# Fluid_Valve_CTRL.net
KiCad netlist of a schematic drawn in Altium Designer
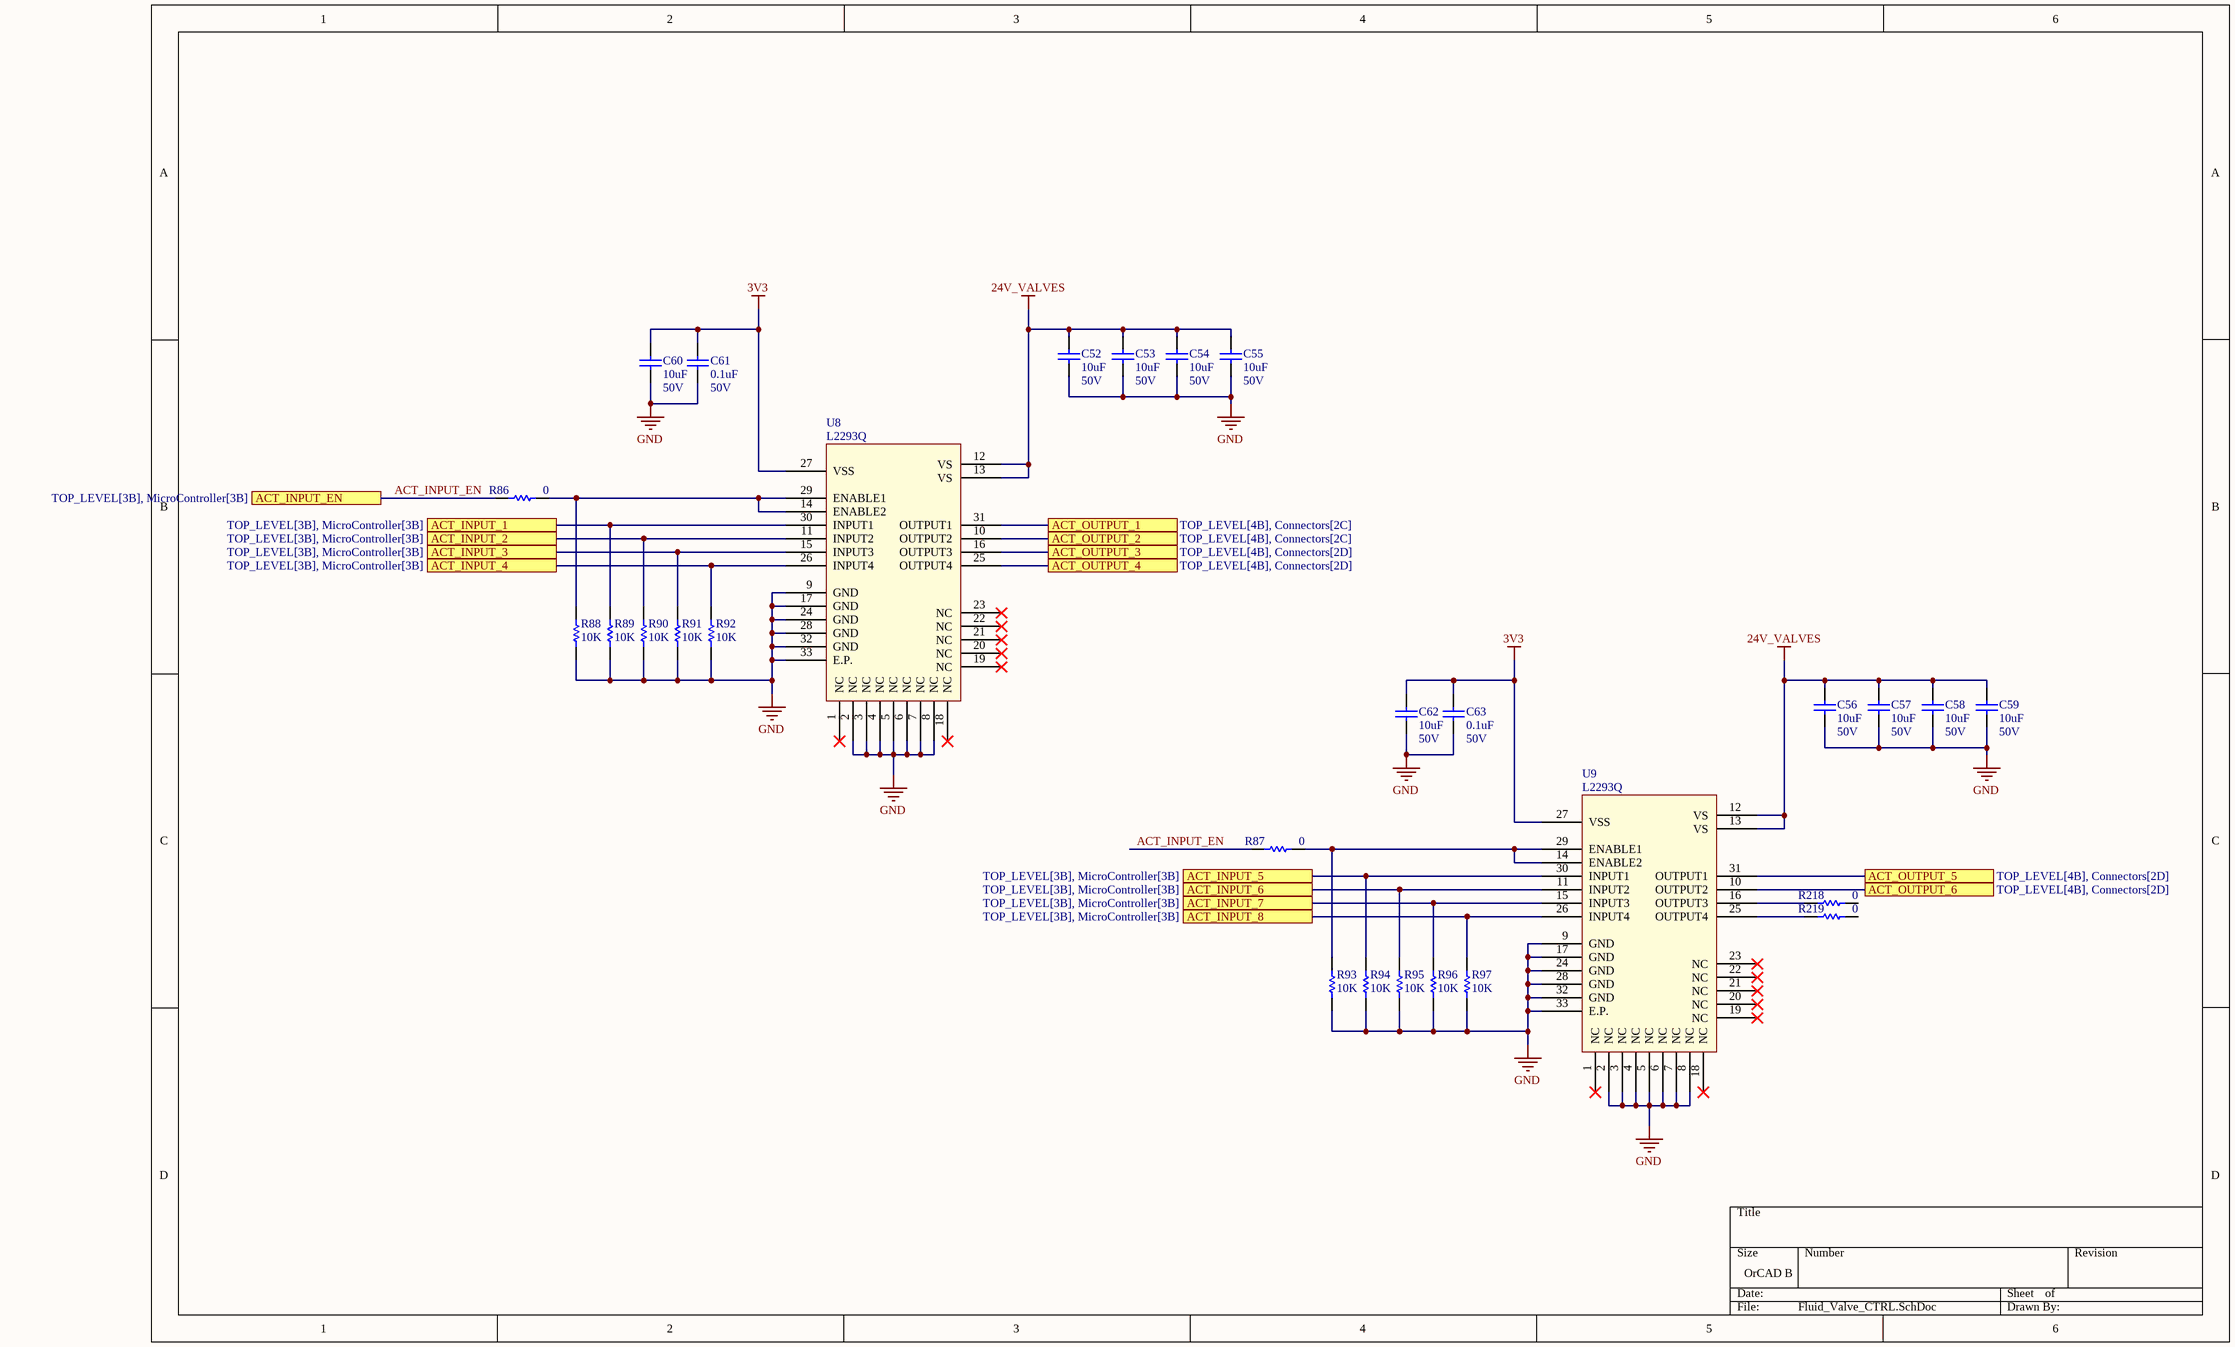
[diagram p0: Fluid_Valve_CTRL.SchDoc]

(export (version "E")
  (design (tool "Eeschema 10.0.6"))
  (components
    (comp (ref "C52")
      (value "10uF")
      (footprint "DEFAULT_CAPACITOR_0805")
      (description "CAP CER 10UF 50V X5R 0805")
      (fields (field (name "RATING") "50V") (field (name "Comment") "GRM21BR61H106KE43L"))
      (libsource (lib "Avery Altium Llibrary") (part "GRM21BR61H106KE43L"))
    )
    (comp (ref "C53")
      (value "10uF")
      (footprint "DEFAULT_CAPACITOR_0805")
      (description "CAP CER 10UF 50V X5R 0805")
      (fields (field (name "RATING") "50V") (field (name "Comment") "GRM21BR61H106KE43L"))
      (libsource (lib "Avery Altium Llibrary") (part "GRM21BR61H106KE43L"))
    )
    (comp (ref "C54")
      (value "10uF")
      (footprint "DEFAULT_CAPACITOR_0805")
      (description "CAP CER 10UF 50V X5R 0805")
      (fields (field (name "RATING") "50V") (field (name "Comment") "GRM21BR61H106KE43L"))
      (libsource (lib "Avery Altium Llibrary") (part "GRM21BR61H106KE43L"))
    )
    (comp (ref "C55")
      (value "10uF")
      (footprint "DEFAULT_CAPACITOR_0805")
      (description "CAP CER 10UF 50V X5R 0805")
      (fields (field (name "RATING") "50V") (field (name "Comment") "GRM21BR61H106KE43L"))
      (libsource (lib "Avery Altium Llibrary") (part "GRM21BR61H106KE43L"))
    )
    (comp (ref "C56")
      (value "10uF")
      (footprint "DEFAULT_CAPACITOR_0805")
      (description "CAP CER 10UF 50V X5R 0805")
      (fields (field (name "RATING") "50V") (field (name "Comment") "GRM21BR61H106KE43L"))
      (libsource (lib "Avery Altium Llibrary") (part "GRM21BR61H106KE43L"))
    )
    (comp (ref "C57")
      (value "10uF")
      (footprint "DEFAULT_CAPACITOR_0805")
      (description "CAP CER 10UF 50V X5R 0805")
      (fields (field (name "RATING") "50V") (field (name "Comment") "GRM21BR61H106KE43L"))
      (libsource (lib "Avery Altium Llibrary") (part "GRM21BR61H106KE43L"))
    )
    (comp (ref "C58")
      (value "10uF")
      (footprint "DEFAULT_CAPACITOR_0805")
      (description "CAP CER 10UF 50V X5R 0805")
      (fields (field (name "RATING") "50V") (field (name "Comment") "GRM21BR61H106KE43L"))
      (libsource (lib "Avery Altium Llibrary") (part "GRM21BR61H106KE43L"))
    )
    (comp (ref "C59")
      (value "10uF")
      (footprint "DEFAULT_CAPACITOR_0805")
      (description "CAP CER 10UF 50V X5R 0805")
      (fields (field (name "RATING") "50V") (field (name "Comment") "GRM21BR61H106KE43L"))
      (libsource (lib "Avery Altium Llibrary") (part "GRM21BR61H106KE43L"))
    )
    (comp (ref "C60")
      (value "10uF")
      (footprint "DEFAULT_CAPACITOR_0805")
      (description "CAP CER 10UF 50V X5R 0805")
      (fields (field (name "RATING") "50V") (field (name "Comment") "GRM21BR61H106KE43L"))
      (libsource (lib "Avery Altium Llibrary") (part "GRM21BR61H106KE43L"))
    )
    (comp (ref "C61")
      (value "0.1uF")
      (footprint "DEFAULT_CAPACITOR_0805")
      (description "CAP CER 0.1UF 50V X7R 0805")
      (fields
        (field (name "MANUFACTURER") "Cal-Chip Electronics, Inc.")
        (field (name "RATING") "50V")
        (field (name "Comment") "KGM21NR71H104KT")
      )
      (libsource (lib "Avery Altium Llibrary") (part "KGM21NR71H104KT"))
    )
    (comp (ref "C62")
      (value "10uF")
      (footprint "DEFAULT_CAPACITOR_0805")
      (description "CAP CER 10UF 50V X5R 0805")
      (fields (field (name "RATING") "50V") (field (name "Comment") "GRM21BR61H106KE43L"))
      (libsource (lib "Avery Altium Llibrary") (part "GRM21BR61H106KE43L"))
    )
    (comp (ref "C63")
      (value "0.1uF")
      (footprint "DEFAULT_CAPACITOR_0805")
      (description "CAP CER 0.1UF 50V X7R 0805")
      (fields
        (field (name "MANUFACTURER") "Cal-Chip Electronics, Inc.")
        (field (name "RATING") "50V")
        (field (name "Comment") "KGM21NR71H104KT")
      )
      (libsource (lib "Avery Altium Llibrary") (part "KGM21NR71H104KT"))
    )
    (comp (ref "R86")
      (value "0")
      (footprint "DEFAULT_RESISTOR_0805")
      (description "RES 0 OHM JUMPER 1/8W 0805")
      (fields (field (name "POWER") "1/8W") (field (name "Comment") "RC0805JR-070RL"))
      (libsource (lib "Avery Altium Llibrary") (part "RC0805JR-070RL"))
    )
    (comp (ref "R87")
      (value "0")
      (footprint "DEFAULT_RESISTOR_0805")
      (description "RES 0 OHM JUMPER 1/8W 0805")
      (fields (field (name "POWER") "1/8W") (field (name "Comment") "RC0805JR-070RL"))
      (libsource (lib "Avery Altium Llibrary") (part "RC0805JR-070RL"))
    )
    (comp (ref "R88")
      (value "10K")
      (footprint "DEFAULT_RESISTOR_0805")
      (description "RES SMD 10K OHM 1% 1/4W 0805")
      (fields (field (name "POWER") "1/4W") (field (name "TOLERANCE") "1%"))
      (libsource (lib "Avery Altium Llibrary") (part "CRCW080510K0FKEA"))
    )
    (comp (ref "R89")
      (value "10K")
      (footprint "DEFAULT_RESISTOR_0805")
      (description "RES SMD 10K OHM 1% 1/4W 0805")
      (fields (field (name "POWER") "1/4W") (field (name "TOLERANCE") "1%"))
      (libsource (lib "Avery Altium Llibrary") (part "CRCW080510K0FKEA"))
    )
    (comp (ref "R90")
      (value "10K")
      (footprint "DEFAULT_RESISTOR_0805")
      (description "RES SMD 10K OHM 1% 1/4W 0805")
      (fields (field (name "POWER") "1/4W") (field (name "TOLERANCE") "1%"))
      (libsource (lib "Avery Altium Llibrary") (part "CRCW080510K0FKEA"))
    )
    (comp (ref "R91")
      (value "10K")
      (footprint "DEFAULT_RESISTOR_0805")
      (description "RES SMD 10K OHM 1% 1/4W 0805")
      (fields (field (name "POWER") "1/4W") (field (name "TOLERANCE") "1%"))
      (libsource (lib "Avery Altium Llibrary") (part "CRCW080510K0FKEA"))
    )
    (comp (ref "R92")
      (value "10K")
      (footprint "DEFAULT_RESISTOR_0805")
      (description "RES SMD 10K OHM 1% 1/4W 0805")
      (fields (field (name "POWER") "1/4W") (field (name "TOLERANCE") "1%"))
      (libsource (lib "Avery Altium Llibrary") (part "CRCW080510K0FKEA"))
    )
    (comp (ref "R93")
      (value "10K")
      (footprint "DEFAULT_RESISTOR_0805")
      (description "RES SMD 10K OHM 1% 1/4W 0805")
      (fields (field (name "POWER") "1/4W") (field (name "TOLERANCE") "1%"))
      (libsource (lib "Avery Altium Llibrary") (part "CRCW080510K0FKEA"))
    )
    (comp (ref "R94")
      (value "10K")
      (footprint "DEFAULT_RESISTOR_0805")
      (description "RES SMD 10K OHM 1% 1/4W 0805")
      (fields (field (name "POWER") "1/4W") (field (name "TOLERANCE") "1%"))
      (libsource (lib "Avery Altium Llibrary") (part "CRCW080510K0FKEA"))
    )
    (comp (ref "R95")
      (value "10K")
      (footprint "DEFAULT_RESISTOR_0805")
      (description "RES SMD 10K OHM 1% 1/4W 0805")
      (fields (field (name "POWER") "1/4W") (field (name "TOLERANCE") "1%"))
      (libsource (lib "Avery Altium Llibrary") (part "CRCW080510K0FKEA"))
    )
    (comp (ref "R96")
      (value "10K")
      (footprint "DEFAULT_RESISTOR_0805")
      (description "RES SMD 10K OHM 1% 1/4W 0805")
      (fields (field (name "POWER") "1/4W") (field (name "TOLERANCE") "1%"))
      (libsource (lib "Avery Altium Llibrary") (part "CRCW080510K0FKEA"))
    )
    (comp (ref "R97")
      (value "10K")
      (footprint "DEFAULT_RESISTOR_0805")
      (description "RES SMD 10K OHM 1% 1/4W 0805")
      (fields (field (name "POWER") "1/4W") (field (name "TOLERANCE") "1%"))
      (libsource (lib "Avery Altium Llibrary") (part "CRCW080510K0FKEA"))
    )
    (comp (ref "R218")
      (value "0")
      (footprint "DEFAULT_RESISTOR_0805")
      (description "RES 0 OHM JUMPER 1/8W 0805")
      (fields (field (name "POWER") "1/8W") (field (name "Comment") "RC0805JR-070RL"))
      (libsource (lib "Avery Altium Llibrary") (part "RC0805JR-070RL"))
    )
    (comp (ref "R219")
      (value "0")
      (footprint "DEFAULT_RESISTOR_0805")
      (description "RES 0 OHM JUMPER 1/8W 0805")
      (fields (field (name "POWER") "1/8W") (field (name "Comment") "RC0805JR-070RL"))
      (libsource (lib "Avery Altium Llibrary") (part "RC0805JR-070RL"))
    )
    (comp (ref "U8")
      (value "L2293Q")
      (footprint "L2293Q")
      (description "IC HALF BRIDG DRV 600MA 32VFQFPN")
      (fields (field (name "MANUFACTURER") "STMicroelectronics") (field (name "MANUFACTURER P/N") "L2293Q"))
      (libsource (lib "Avery Altium Llibrary") (part "L2293Q"))
    )
    (comp (ref "U9")
      (value "L2293Q")
      (footprint "L2293Q")
      (description "IC HALF BRIDG DRV 600MA 32VFQFPN")
      (fields (field (name "MANUFACTURER") "STMicroelectronics") (field (name "MANUFACTURER P/N") "L2293Q"))
      (libsource (lib "Avery Altium Llibrary") (part "L2293Q"))
    )
  )
  (nets
    (net (code "1") (name "/ACT_INPUT_1") (class "Default")
      (node (ref "R89") (pin "1") (pinfunction "1_1") (pintype "passive"))
      (node (ref "U8") (pin "30") (pinfunction "INPUT1_30") (pintype "passive"))
    )
    (net (code "2") (name "/ACT_INPUT_2") (class "Default")
      (node (ref "R90") (pin "1") (pinfunction "1_1") (pintype "passive"))
      (node (ref "U8") (pin "11") (pinfunction "INPUT2_11") (pintype "passive"))
    )
    (net (code "3") (name "/ACT_INPUT_3") (class "Default")
      (node (ref "R91") (pin "1") (pinfunction "1_1") (pintype "passive"))
      (node (ref "U8") (pin "15") (pinfunction "INPUT3_15") (pintype "passive"))
    )
    (net (code "4") (name "/ACT_INPUT_4") (class "Default")
      (node (ref "R92") (pin "1") (pinfunction "1_1") (pintype "passive"))
      (node (ref "U8") (pin "26") (pinfunction "INPUT4_26") (pintype "passive"))
    )
    (net (code "5") (name "/ACT_INPUT_5") (class "Default")
      (node (ref "R94") (pin "1") (pinfunction "1_1") (pintype "passive"))
      (node (ref "U9") (pin "30") (pinfunction "INPUT1_30") (pintype "passive"))
    )
    (net (code "6") (name "/ACT_INPUT_6") (class "Default")
      (node (ref "R95") (pin "1") (pinfunction "1_1") (pintype "passive"))
      (node (ref "U9") (pin "11") (pinfunction "INPUT2_11") (pintype "passive"))
    )
    (net (code "7") (name "/ACT_INPUT_7") (class "Default")
      (node (ref "R96") (pin "1") (pinfunction "1_1") (pintype "passive"))
      (node (ref "U9") (pin "15") (pinfunction "INPUT3_15") (pintype "passive"))
    )
    (net (code "8") (name "/ACT_INPUT_8") (class "Default")
      (node (ref "R97") (pin "1") (pinfunction "1_1") (pintype "passive"))
      (node (ref "U9") (pin "26") (pinfunction "INPUT4_26") (pintype "passive"))
    )
    (net (code "9") (name "/ACT_INPUT_EN") (class "Default")
      (node (ref "R86") (pin "2") (pinfunction "2_2") (pintype "passive"))
      (node (ref "R87") (pin "2") (pinfunction "2_2") (pintype "passive"))
    )
    (net (code "10") (name "/ACT_OUTPUT_1") (class "Default")
      (node (ref "U8") (pin "31") (pinfunction "OUTPUT1_31") (pintype "passive"))
    )
    (net (code "11") (name "/ACT_OUTPUT_2") (class "Default")
      (node (ref "U8") (pin "10") (pinfunction "OUTPUT2_10") (pintype "passive"))
    )
    (net (code "12") (name "/ACT_OUTPUT_3") (class "Default")
      (node (ref "U8") (pin "16") (pinfunction "OUTPUT3_16") (pintype "passive"))
    )
    (net (code "13") (name "/ACT_OUTPUT_4") (class "Default")
      (node (ref "U8") (pin "25") (pinfunction "OUTPUT4_25") (pintype "passive"))
    )
    (net (code "14") (name "/ACT_OUTPUT_5") (class "Default")
      (node (ref "U9") (pin "31") (pinfunction "OUTPUT1_31") (pintype "passive"))
    )
    (net (code "15") (name "/ACT_OUTPUT_6") (class "Default")
      (node (ref "U9") (pin "10") (pinfunction "OUTPUT2_10") (pintype "passive"))
    )
    (net (code "16") (name "3V3") (class "Default")
      (node (ref "C60") (pin "2") (pinfunction "2_2") (pintype "passive"))
      (node (ref "C61") (pin "2") (pinfunction "2_2") (pintype "passive"))
      (node (ref "C62") (pin "2") (pinfunction "2_2") (pintype "passive"))
      (node (ref "C63") (pin "2") (pinfunction "2_2") (pintype "passive"))
      (node (ref "U8") (pin "27") (pinfunction "VSS_27") (pintype "passive"))
      (node (ref "U9") (pin "27") (pinfunction "VSS_27") (pintype "passive"))
    )
    (net (code "17") (name "24V_VALVES") (class "Default")
      (node (ref "C52") (pin "2") (pinfunction "2_2") (pintype "passive"))
      (node (ref "C53") (pin "2") (pinfunction "2_2") (pintype "passive"))
      (node (ref "C54") (pin "2") (pinfunction "2_2") (pintype "passive"))
      (node (ref "C55") (pin "2") (pinfunction "2_2") (pintype "passive"))
      (node (ref "C56") (pin "2") (pinfunction "2_2") (pintype "passive"))
      (node (ref "C57") (pin "2") (pinfunction "2_2") (pintype "passive"))
      (node (ref "C58") (pin "2") (pinfunction "2_2") (pintype "passive"))
      (node (ref "C59") (pin "2") (pinfunction "2_2") (pintype "passive"))
      (node (ref "U8") (pin "12") (pinfunction "VS_12") (pintype "passive"))
      (node (ref "U8") (pin "13") (pinfunction "VS_13") (pintype "passive"))
      (node (ref "U9") (pin "12") (pinfunction "VS_12") (pintype "passive"))
      (node (ref "U9") (pin "13") (pinfunction "VS_13") (pintype "passive"))
    )
    (net (code "18") (name "GND") (class "Default")
      (node (ref "C52") (pin "1") (pinfunction "1_1") (pintype "passive"))
      (node (ref "C53") (pin "1") (pinfunction "1_1") (pintype "passive"))
      (node (ref "C54") (pin "1") (pinfunction "1_1") (pintype "passive"))
      (node (ref "C55") (pin "1") (pinfunction "1_1") (pintype "passive"))
      (node (ref "C56") (pin "1") (pinfunction "1_1") (pintype "passive"))
      (node (ref "C57") (pin "1") (pinfunction "1_1") (pintype "passive"))
      (node (ref "C58") (pin "1") (pinfunction "1_1") (pintype "passive"))
      (node (ref "C59") (pin "1") (pinfunction "1_1") (pintype "passive"))
      (node (ref "C60") (pin "1") (pinfunction "1_1") (pintype "passive"))
      (node (ref "C61") (pin "1") (pinfunction "1_1") (pintype "passive"))
      (node (ref "C62") (pin "1") (pinfunction "1_1") (pintype "passive"))
      (node (ref "C63") (pin "1") (pinfunction "1_1") (pintype "passive"))
      (node (ref "R88") (pin "2") (pinfunction "2_2") (pintype "passive"))
      (node (ref "R89") (pin "2") (pinfunction "2_2") (pintype "passive"))
      (node (ref "R90") (pin "2") (pinfunction "2_2") (pintype "passive"))
      (node (ref "R91") (pin "2") (pinfunction "2_2") (pintype "passive"))
      (node (ref "R92") (pin "2") (pinfunction "2_2") (pintype "passive"))
      (node (ref "R93") (pin "2") (pinfunction "2_2") (pintype "passive"))
      (node (ref "R94") (pin "2") (pinfunction "2_2") (pintype "passive"))
      (node (ref "R95") (pin "2") (pinfunction "2_2") (pintype "passive"))
      (node (ref "R96") (pin "2") (pinfunction "2_2") (pintype "passive"))
      (node (ref "R97") (pin "2") (pinfunction "2_2") (pintype "passive"))
      (node (ref "U8") (pin "17") (pinfunction "GND_17") (pintype "passive"))
      (node (ref "U8") (pin "2") (pinfunction "NC_2") (pintype "passive"))
      (node (ref "U8") (pin "24") (pinfunction "GND_24") (pintype "passive"))
      (node (ref "U8") (pin "28") (pinfunction "GND_28") (pintype "passive"))
      (node (ref "U8") (pin "3") (pinfunction "NC_3") (pintype "passive"))
      (node (ref "U8") (pin "32") (pinfunction "GND_32") (pintype "passive"))
      (node (ref "U8") (pin "33") (pinfunction "E.P._33") (pintype "passive"))
      (node (ref "U8") (pin "4") (pinfunction "NC_4") (pintype "passive"))
      (node (ref "U8") (pin "5") (pinfunction "NC_5") (pintype "passive"))
      (node (ref "U8") (pin "6") (pinfunction "NC_6") (pintype "passive"))
      (node (ref "U8") (pin "7") (pinfunction "NC_7") (pintype "passive"))
      (node (ref "U8") (pin "8") (pinfunction "NC_8") (pintype "passive"))
      (node (ref "U8") (pin "9") (pinfunction "GND_9") (pintype "passive"))
      (node (ref "U9") (pin "17") (pinfunction "GND_17") (pintype "passive"))
      (node (ref "U9") (pin "2") (pinfunction "NC_2") (pintype "passive"))
      (node (ref "U9") (pin "24") (pinfunction "GND_24") (pintype "passive"))
      (node (ref "U9") (pin "28") (pinfunction "GND_28") (pintype "passive"))
      (node (ref "U9") (pin "3") (pinfunction "NC_3") (pintype "passive"))
      (node (ref "U9") (pin "32") (pinfunction "GND_32") (pintype "passive"))
      (node (ref "U9") (pin "33") (pinfunction "E.P._33") (pintype "passive"))
      (node (ref "U9") (pin "4") (pinfunction "NC_4") (pintype "passive"))
      (node (ref "U9") (pin "5") (pinfunction "NC_5") (pintype "passive"))
      (node (ref "U9") (pin "6") (pinfunction "NC_6") (pintype "passive"))
      (node (ref "U9") (pin "7") (pinfunction "NC_7") (pintype "passive"))
      (node (ref "U9") (pin "8") (pinfunction "NC_8") (pintype "passive"))
      (node (ref "U9") (pin "9") (pinfunction "GND_9") (pintype "passive"))
    )
    (net (code "19") (name "Net-(U8-ENABLE1)") (class "Default")
      (node (ref "R86") (pin "1") (pinfunction "1_1") (pintype "passive"))
      (node (ref "R88") (pin "1") (pinfunction "1_1") (pintype "passive"))
      (node (ref "U8") (pin "14") (pinfunction "ENABLE2_14") (pintype "passive"))
      (node (ref "U8") (pin "29") (pinfunction "ENABLE1_29") (pintype "passive"))
    )
    (net (code "20") (name "Net-(U9-ENABLE1)") (class "Default")
      (node (ref "R87") (pin "1") (pinfunction "1_1") (pintype "passive"))
      (node (ref "R93") (pin "1") (pinfunction "1_1") (pintype "passive"))
      (node (ref "U9") (pin "14") (pinfunction "ENABLE2_14") (pintype "passive"))
      (node (ref "U9") (pin "29") (pinfunction "ENABLE1_29") (pintype "passive"))
    )
    (net (code "21") (name "Net-(U9-OUTPUT3)") (class "Default")
      (node (ref "R218") (pin "2") (pinfunction "2_2") (pintype "passive"))
      (node (ref "U9") (pin "16") (pinfunction "OUTPUT3_16") (pintype "passive"))
    )
    (net (code "22") (name "Net-(U9-OUTPUT4)") (class "Default")
      (node (ref "R219") (pin "2") (pinfunction "2_2") (pintype "passive"))
      (node (ref "U9") (pin "25") (pinfunction "OUTPUT4_25") (pintype "passive"))
    )
    (net (code "23") (name "unconnected-(R218-Pad1)") (class "Default")
      (node (ref "R218") (pin "1") (pinfunction "1_1") (pintype "passive"))
    )
    (net (code "24") (name "unconnected-(R219-Pad1)") (class "Default")
      (node (ref "R219") (pin "1") (pinfunction "1_1") (pintype "passive"))
    )
    (net (code "25") (name "unconnected-(U8-NC-Pad1)") (class "Default")
      (node (ref "U8") (pin "1") (pinfunction "NC_1") (pintype "passive+no_connect"))
    )
    (net (code "26") (name "unconnected-(U8-NC-Pad18)") (class "Default")
      (node (ref "U8") (pin "18") (pinfunction "NC_18") (pintype "passive+no_connect"))
    )
    (net (code "27") (name "unconnected-(U8-NC-Pad19)") (class "Default")
      (node (ref "U8") (pin "19") (pinfunction "NC_19") (pintype "passive+no_connect"))
    )
    (net (code "28") (name "unconnected-(U8-NC-Pad20)") (class "Default")
      (node (ref "U8") (pin "20") (pinfunction "NC_20") (pintype "passive+no_connect"))
    )
    (net (code "29") (name "unconnected-(U8-NC-Pad21)") (class "Default")
      (node (ref "U8") (pin "21") (pinfunction "NC_21") (pintype "passive+no_connect"))
    )
    (net (code "30") (name "unconnected-(U8-NC-Pad22)") (class "Default")
      (node (ref "U8") (pin "22") (pinfunction "NC_22") (pintype "passive+no_connect"))
    )
    (net (code "31") (name "unconnected-(U8-NC-Pad23)") (class "Default")
      (node (ref "U8") (pin "23") (pinfunction "NC_23") (pintype "passive+no_connect"))
    )
    (net (code "32") (name "unconnected-(U9-NC-Pad1)") (class "Default")
      (node (ref "U9") (pin "1") (pinfunction "NC_1") (pintype "passive+no_connect"))
    )
    (net (code "33") (name "unconnected-(U9-NC-Pad18)") (class "Default")
      (node (ref "U9") (pin "18") (pinfunction "NC_18") (pintype "passive+no_connect"))
    )
    (net (code "34") (name "unconnected-(U9-NC-Pad19)") (class "Default")
      (node (ref "U9") (pin "19") (pinfunction "NC_19") (pintype "passive+no_connect"))
    )
    (net (code "35") (name "unconnected-(U9-NC-Pad20)") (class "Default")
      (node (ref "U9") (pin "20") (pinfunction "NC_20") (pintype "passive+no_connect"))
    )
    (net (code "36") (name "unconnected-(U9-NC-Pad21)") (class "Default")
      (node (ref "U9") (pin "21") (pinfunction "NC_21") (pintype "passive+no_connect"))
    )
    (net (code "37") (name "unconnected-(U9-NC-Pad22)") (class "Default")
      (node (ref "U9") (pin "22") (pinfunction "NC_22") (pintype "passive+no_connect"))
    )
    (net (code "38") (name "unconnected-(U9-NC-Pad23)") (class "Default")
      (node (ref "U9") (pin "23") (pinfunction "NC_23") (pintype "passive+no_connect"))
    )
  )
)
